# LEDS.net
KiCad netlist of a schematic drawn in Altium Designer
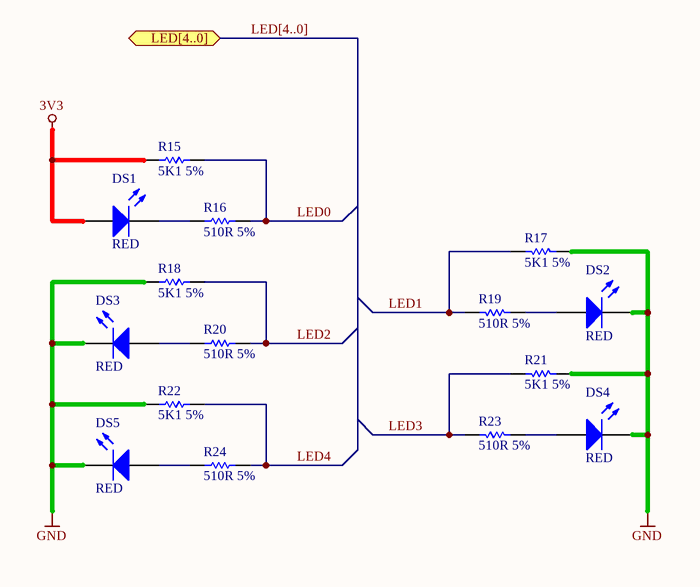
[diagram p0: LEDS.SchDoc]

(export (version "E")
  (design (tool "Eeschema 10.0.6"))
  (components
    (comp (ref "DS1")
      (value "RED")
      (footprint "LED2013")
      (description "Typical GREEN SMD LED Agilent make")
      (libsource (lib "PHY") (part "DIO-LED-1S"))
    )
    (comp (ref "DS2")
      (value "RED")
      (footprint "LED2013")
      (description "Typical GREEN SMD LED Agilent make")
      (libsource (lib "PHY") (part "DIO-LED-1S"))
    )
    (comp (ref "DS3")
      (value "RED")
      (footprint "LED2013")
      (description "Typical GREEN SMD LED Agilent make")
      (libsource (lib "PHY") (part "DIO-LED-1S"))
    )
    (comp (ref "DS4")
      (value "RED")
      (footprint "LED2013")
      (description "Typical GREEN SMD LED Agilent make")
      (libsource (lib "PHY") (part "DIO-LED-1S"))
    )
    (comp (ref "DS5")
      (value "RED")
      (footprint "LED2013")
      (description "Typical GREEN SMD LED Agilent make")
      (libsource (lib "PHY") (part "DIO-LED-1S"))
    )
    (comp (ref "R15")
      (value "5K1 5%")
      (footprint "RESC2012")
      (description "Resistor")
      (libsource (lib "PHY") (part "RES"))
    )
    (comp (ref "R16")
      (value "510R 5%")
      (footprint "RESC2012")
      (description "Resistor")
      (libsource (lib "PHY") (part "RES"))
    )
    (comp (ref "R17")
      (value "5K1 5%")
      (footprint "RESC2012")
      (description "Resistor")
      (libsource (lib "PHY") (part "RES"))
    )
    (comp (ref "R18")
      (value "5K1 5%")
      (footprint "RESC2012")
      (description "Resistor")
      (libsource (lib "PHY") (part "RES"))
    )
    (comp (ref "R19")
      (value "510R 5%")
      (footprint "RESC2012")
      (description "Resistor")
      (libsource (lib "PHY") (part "RES"))
    )
    (comp (ref "R20")
      (value "510R 5%")
      (footprint "RESC2012")
      (description "Resistor")
      (libsource (lib "PHY") (part "RES"))
    )
    (comp (ref "R21")
      (value "5K1 5%")
      (footprint "RESC2012")
      (description "Resistor")
      (libsource (lib "PHY") (part "RES"))
    )
    (comp (ref "R22")
      (value "5K1 5%")
      (footprint "RESC2012")
      (description "Resistor")
      (libsource (lib "PHY") (part "RES"))
    )
    (comp (ref "R23")
      (value "510R 5%")
      (footprint "RESC2012")
      (description "Resistor")
      (libsource (lib "PHY") (part "RES"))
    )
    (comp (ref "R24")
      (value "510R 5%")
      (footprint "RESC2012")
      (description "Resistor")
      (libsource (lib "PHY") (part "RES"))
    )
  )
  (nets
    (net (code "1") (name "/LED0") (class "Default")
      (node (ref "R15") (pin "2") (pinfunction "2_2") (pintype "passive"))
      (node (ref "R16") (pin "2") (pinfunction "2_2") (pintype "passive"))
    )
    (net (code "2") (name "/LED1") (class "Default")
      (node (ref "R17") (pin "2") (pinfunction "2_2") (pintype "passive"))
      (node (ref "R19") (pin "2") (pinfunction "2_2") (pintype "passive"))
    )
    (net (code "3") (name "/LED2") (class "Default")
      (node (ref "R18") (pin "2") (pinfunction "2_2") (pintype "passive"))
      (node (ref "R20") (pin "2") (pinfunction "2_2") (pintype "passive"))
    )
    (net (code "4") (name "/LED3") (class "Default")
      (node (ref "R21") (pin "2") (pinfunction "2_2") (pintype "passive"))
      (node (ref "R23") (pin "2") (pinfunction "2_2") (pintype "passive"))
    )
    (net (code "5") (name "/LED4") (class "Default")
      (node (ref "R22") (pin "2") (pinfunction "2_2") (pintype "passive"))
      (node (ref "R24") (pin "2") (pinfunction "2_2") (pintype "passive"))
    )
    (net (code "7") (name "3V3") (class "Default")
      (node (ref "DS1") (pin "1") (pinfunction "A_1") (pintype "passive"))
      (node (ref "R15") (pin "1") (pinfunction "1_1") (pintype "passive"))
    )
    (net (code "8") (name "GND") (class "Default")
      (node (ref "DS2") (pin "2") (pinfunction "K_2") (pintype "passive"))
      (node (ref "DS3") (pin "2") (pinfunction "K_2") (pintype "passive"))
      (node (ref "DS4") (pin "2") (pinfunction "K_2") (pintype "passive"))
      (node (ref "DS5") (pin "2") (pinfunction "K_2") (pintype "passive"))
      (node (ref "R17") (pin "1") (pinfunction "1_1") (pintype "passive"))
      (node (ref "R18") (pin "1") (pinfunction "1_1") (pintype "passive"))
      (node (ref "R21") (pin "1") (pinfunction "1_1") (pintype "passive"))
      (node (ref "R22") (pin "1") (pinfunction "1_1") (pintype "passive"))
    )
    (net (code "9") (name "Net-(DS1-K)") (class "Default")
      (node (ref "DS1") (pin "2") (pinfunction "K_2") (pintype "passive"))
      (node (ref "R16") (pin "1") (pinfunction "1_1") (pintype "passive"))
    )
    (net (code "10") (name "Net-(DS2-A)") (class "Default")
      (node (ref "DS2") (pin "1") (pinfunction "A_1") (pintype "passive"))
      (node (ref "R19") (pin "1") (pinfunction "1_1") (pintype "passive"))
    )
    (net (code "11") (name "Net-(DS3-A)") (class "Default")
      (node (ref "DS3") (pin "1") (pinfunction "A_1") (pintype "passive"))
      (node (ref "R20") (pin "1") (pinfunction "1_1") (pintype "passive"))
    )
    (net (code "12") (name "Net-(DS4-A)") (class "Default")
      (node (ref "DS4") (pin "1") (pinfunction "A_1") (pintype "passive"))
      (node (ref "R23") (pin "1") (pinfunction "1_1") (pintype "passive"))
    )
    (net (code "13") (name "Net-(DS5-A)") (class "Default")
      (node (ref "DS5") (pin "1") (pinfunction "A_1") (pintype "passive"))
      (node (ref "R24") (pin "1") (pinfunction "1_1") (pintype "passive"))
    )
  )
)
